# RS232_9x.net
KiCad netlist of a schematic drawn in EAGLE
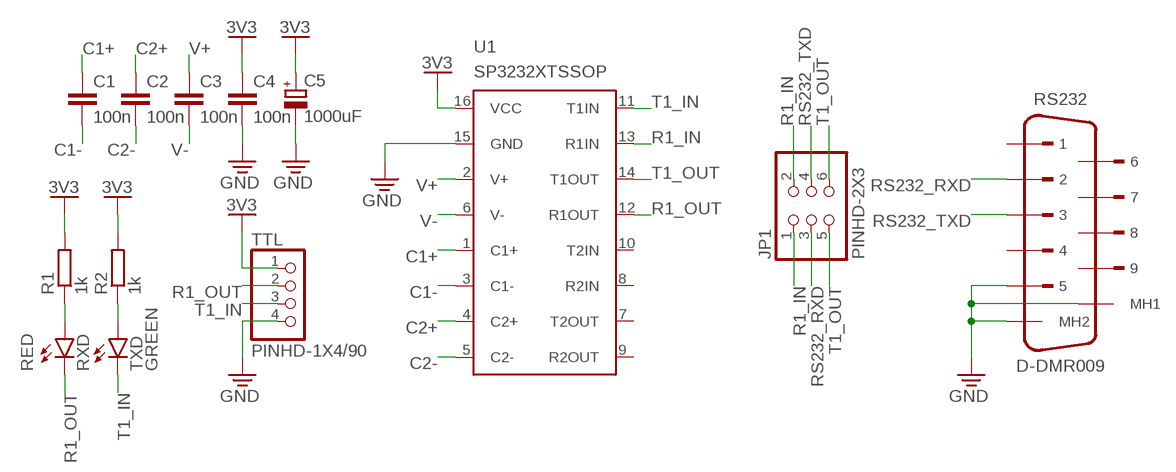
[diagram p0: schematic, sheet 1]

(export (version "E")
  (design (tool "Eeschema 10.0.6"))
  (components
    (comp (ref "C1")
      (value "100n")
      (footprint "eagle-import:C0402")
      (libsource (lib "eagle-import") (part "C-EUC0402"))
    )
    (comp (ref "C2")
      (value "100n")
      (footprint "eagle-import:C0402")
      (libsource (lib "eagle-import") (part "C-EUC0402"))
    )
    (comp (ref "C3")
      (value "100n")
      (footprint "eagle-import:C0402")
      (libsource (lib "eagle-import") (part "C-EUC0402"))
    )
    (comp (ref "C4")
      (value "100n")
      (footprint "eagle-import:C0402")
      (libsource (lib "eagle-import") (part "C-EUC0402"))
    )
    (comp (ref "C5")
      (value "1000uF")
      (footprint "eagle-import:140CLH-1010")
      (libsource (lib "eagle-import") (part "CPOL-EU140CLH-1010"))
    )
    (comp (ref "JP1")
      (value "PINHD-2X3")
      (footprint "eagle-import:2X03")
      (fields (field (name "MANUFACTURER") "Generic"))
      (libsource (lib "eagle-import") (part "PINHD-2X3"))
    )
    (comp (ref "R1")
      (value "1k")
      (footprint "eagle-import:R0402")
      (libsource (lib "eagle-import") (part "R-EU_R0402"))
    )
    (comp (ref "R2")
      (value "1k")
      (footprint "eagle-import:R0402")
      (libsource (lib "eagle-import") (part "R-EU_R0402"))
    )
    (comp (ref "RS232")
      (value "D-DMR009")
      (footprint "eagle-import:5747840-4")
      (fields (field (name "MANUFACTURER") "TE Connectivity") (field (name "MPN") "5747840-4"))
      (libsource (lib "eagle-import") (part "5747840{dblquote}"))
    )
    (comp (ref "RXD")
      (value "RED")
      (footprint "eagle-import:CHIP-LED0603")
      (libsource (lib "eagle-import") (part "LEDCHIP-LED0603"))
    )
    (comp (ref "TTL")
      (value "PINHD-1X4/90")
      (footprint "eagle-import:1X04_90")
      (fields (field (name "MANUFACTURER") "Generic"))
      (libsource (lib "eagle-import") (part "PINHD-1X4/90"))
    )
    (comp (ref "TXD")
      (value "GREEN")
      (footprint "eagle-import:CHIP-LED0603")
      (libsource (lib "eagle-import") (part "LEDCHIP-LED0603"))
    )
    (comp (ref "U1")
      (value "SP3232XTSSOP")
      (footprint "eagle-import:TSSOP16")
      (libsource (lib "eagle-import") (part "SP3232XTSSOP"))
    )
  )
  (nets
    (net (code "1") (name "/C1+") (class "Default")
      (node (ref "C1") (pin "1") (pinfunction "1_1") (pintype "passive"))
      (node (ref "U1") (pin "1") (pinfunction "C1+_1") (pintype "bidirectional"))
    )
    (net (code "2") (name "/C1-") (class "Default")
      (node (ref "C1") (pin "2") (pinfunction "2_2") (pintype "passive"))
      (node (ref "U1") (pin "3") (pinfunction "C1-_3") (pintype "bidirectional"))
    )
    (net (code "3") (name "/C2+") (class "Default")
      (node (ref "C2") (pin "1") (pinfunction "1_1") (pintype "passive"))
      (node (ref "U1") (pin "4") (pinfunction "C2+_4") (pintype "bidirectional"))
    )
    (net (code "4") (name "/C2-") (class "Default")
      (node (ref "C2") (pin "2") (pinfunction "2_2") (pintype "passive"))
      (node (ref "U1") (pin "5") (pinfunction "C2-_5") (pintype "bidirectional"))
    )
    (net (code "5") (name "/R1_IN") (class "Default")
      (node (ref "JP1") (pin "1") (pinfunction "1_1") (pintype "passive"))
      (node (ref "JP1") (pin "2") (pinfunction "2_2") (pintype "passive"))
      (node (ref "U1") (pin "13") (pinfunction "R1IN_13") (pintype "input"))
    )
    (net (code "6") (name "/R1_OUT") (class "Default")
      (node (ref "RXD") (pin "C") (pinfunction "C_C") (pintype "passive"))
      (node (ref "TTL") (pin "2") (pinfunction "2_2") (pintype "passive"))
      (node (ref "U1") (pin "12") (pinfunction "R1OUT_12") (pintype "output"))
    )
    (net (code "7") (name "/RS232_RXD") (class "Default")
      (node (ref "JP1") (pin "3") (pinfunction "3_3") (pintype "passive"))
      (node (ref "RS232") (pin "2") (pinfunction "2_2") (pintype "passive"))
    )
    (net (code "8") (name "/RS232_TXD") (class "Default")
      (node (ref "JP1") (pin "4") (pinfunction "4_4") (pintype "passive"))
      (node (ref "RS232") (pin "3") (pinfunction "3_3") (pintype "passive"))
    )
    (net (code "9") (name "/T1_IN") (class "Default")
      (node (ref "TTL") (pin "3") (pinfunction "3_3") (pintype "passive"))
      (node (ref "TXD") (pin "C") (pinfunction "C_C") (pintype "passive"))
      (node (ref "U1") (pin "11") (pinfunction "T1IN_11") (pintype "input"))
    )
    (net (code "10") (name "/T1_OUT") (class "Default")
      (node (ref "JP1") (pin "5") (pinfunction "5_5") (pintype "passive"))
      (node (ref "JP1") (pin "6") (pinfunction "6_6") (pintype "passive"))
      (node (ref "U1") (pin "14") (pinfunction "T1OUT_14") (pintype "output"))
    )
    (net (code "11") (name "/V+") (class "Default")
      (node (ref "C3") (pin "1") (pinfunction "1_1") (pintype "passive"))
      (node (ref "U1") (pin "2") (pinfunction "V+_2") (pintype "power_in"))
    )
    (net (code "12") (name "/V-") (class "Default")
      (node (ref "C3") (pin "2") (pinfunction "2_2") (pintype "passive"))
      (node (ref "U1") (pin "6") (pinfunction "V-_6") (pintype "power_in"))
    )
    (net (code "13") (name "3V3") (class "Default")
      (node (ref "C4") (pin "1") (pinfunction "1_1") (pintype "passive"))
      (node (ref "C5") (pin "+") (pinfunction "+_+") (pintype "passive"))
      (node (ref "R1") (pin "2") (pinfunction "2_2") (pintype "passive"))
      (node (ref "R2") (pin "2") (pinfunction "2_2") (pintype "passive"))
      (node (ref "TTL") (pin "1") (pinfunction "1_1") (pintype "passive"))
      (node (ref "U1") (pin "16") (pinfunction "VCC_16") (pintype "power_in"))
    )
    (net (code "14") (name "GND") (class "Default")
      (node (ref "C4") (pin "2") (pinfunction "2_2") (pintype "passive"))
      (node (ref "C5") (pin "-") (pinfunction "-_-") (pintype "passive"))
      (node (ref "RS232") (pin "5") (pinfunction "5_5") (pintype "passive"))
      (node (ref "RS232") (pin "MH1") (pinfunction "MH2_MH1") (pintype "power_in"))
      (node (ref "RS232") (pin "MH2") (pinfunction "MH1_MH2") (pintype "power_in"))
      (node (ref "TTL") (pin "4") (pinfunction "4_4") (pintype "passive"))
      (node (ref "U1") (pin "15") (pinfunction "GND_15") (pintype "power_in"))
    )
    (net (code "15") (name "Net-(R1-Pad1)") (class "Default")
      (node (ref "R1") (pin "1") (pinfunction "1_1") (pintype "passive"))
      (node (ref "RXD") (pin "A") (pinfunction "A_A") (pintype "passive"))
    )
    (net (code "16") (name "Net-(R2-Pad1)") (class "Default")
      (node (ref "R2") (pin "1") (pinfunction "1_1") (pintype "passive"))
      (node (ref "TXD") (pin "A") (pinfunction "A_A") (pintype "passive"))
    )
    (net (code "17") (name "unconnected-(RS232-Pad1)") (class "Default")
      (node (ref "RS232") (pin "1") (pinfunction "1_1") (pintype "passive"))
    )
    (net (code "18") (name "unconnected-(RS232-Pad4)") (class "Default")
      (node (ref "RS232") (pin "4") (pinfunction "4_4") (pintype "passive"))
    )
    (net (code "19") (name "unconnected-(RS232-Pad6)") (class "Default")
      (node (ref "RS232") (pin "6") (pinfunction "6_6") (pintype "passive"))
    )
    (net (code "20") (name "unconnected-(RS232-Pad7)") (class "Default")
      (node (ref "RS232") (pin "7") (pinfunction "7_7") (pintype "passive"))
    )
    (net (code "21") (name "unconnected-(RS232-Pad8)") (class "Default")
      (node (ref "RS232") (pin "8") (pinfunction "8_8") (pintype "passive"))
    )
    (net (code "22") (name "unconnected-(RS232-Pad9)") (class "Default")
      (node (ref "RS232") (pin "9") (pinfunction "9_9") (pintype "passive"))
    )
    (net (code "23") (name "unconnected-(U1-R2IN-Pad8)") (class "Default")
      (node (ref "U1") (pin "8") (pinfunction "R2IN_8") (pintype "input"))
    )
    (net (code "24") (name "unconnected-(U1-R2OUT-Pad9)") (class "Default")
      (node (ref "U1") (pin "9") (pinfunction "R2OUT_9") (pintype "output"))
    )
    (net (code "25") (name "unconnected-(U1-T2IN-Pad10)") (class "Default")
      (node (ref "U1") (pin "10") (pinfunction "T2IN_10") (pintype "input"))
    )
    (net (code "26") (name "unconnected-(U1-T2OUT-Pad7)") (class "Default")
      (node (ref "U1") (pin "7") (pinfunction "T2OUT_7") (pintype "output"))
    )
  )
)
